# zx_tcp_serial.net
KiCad netlist of a schematic drawn in EasyEDA Pro
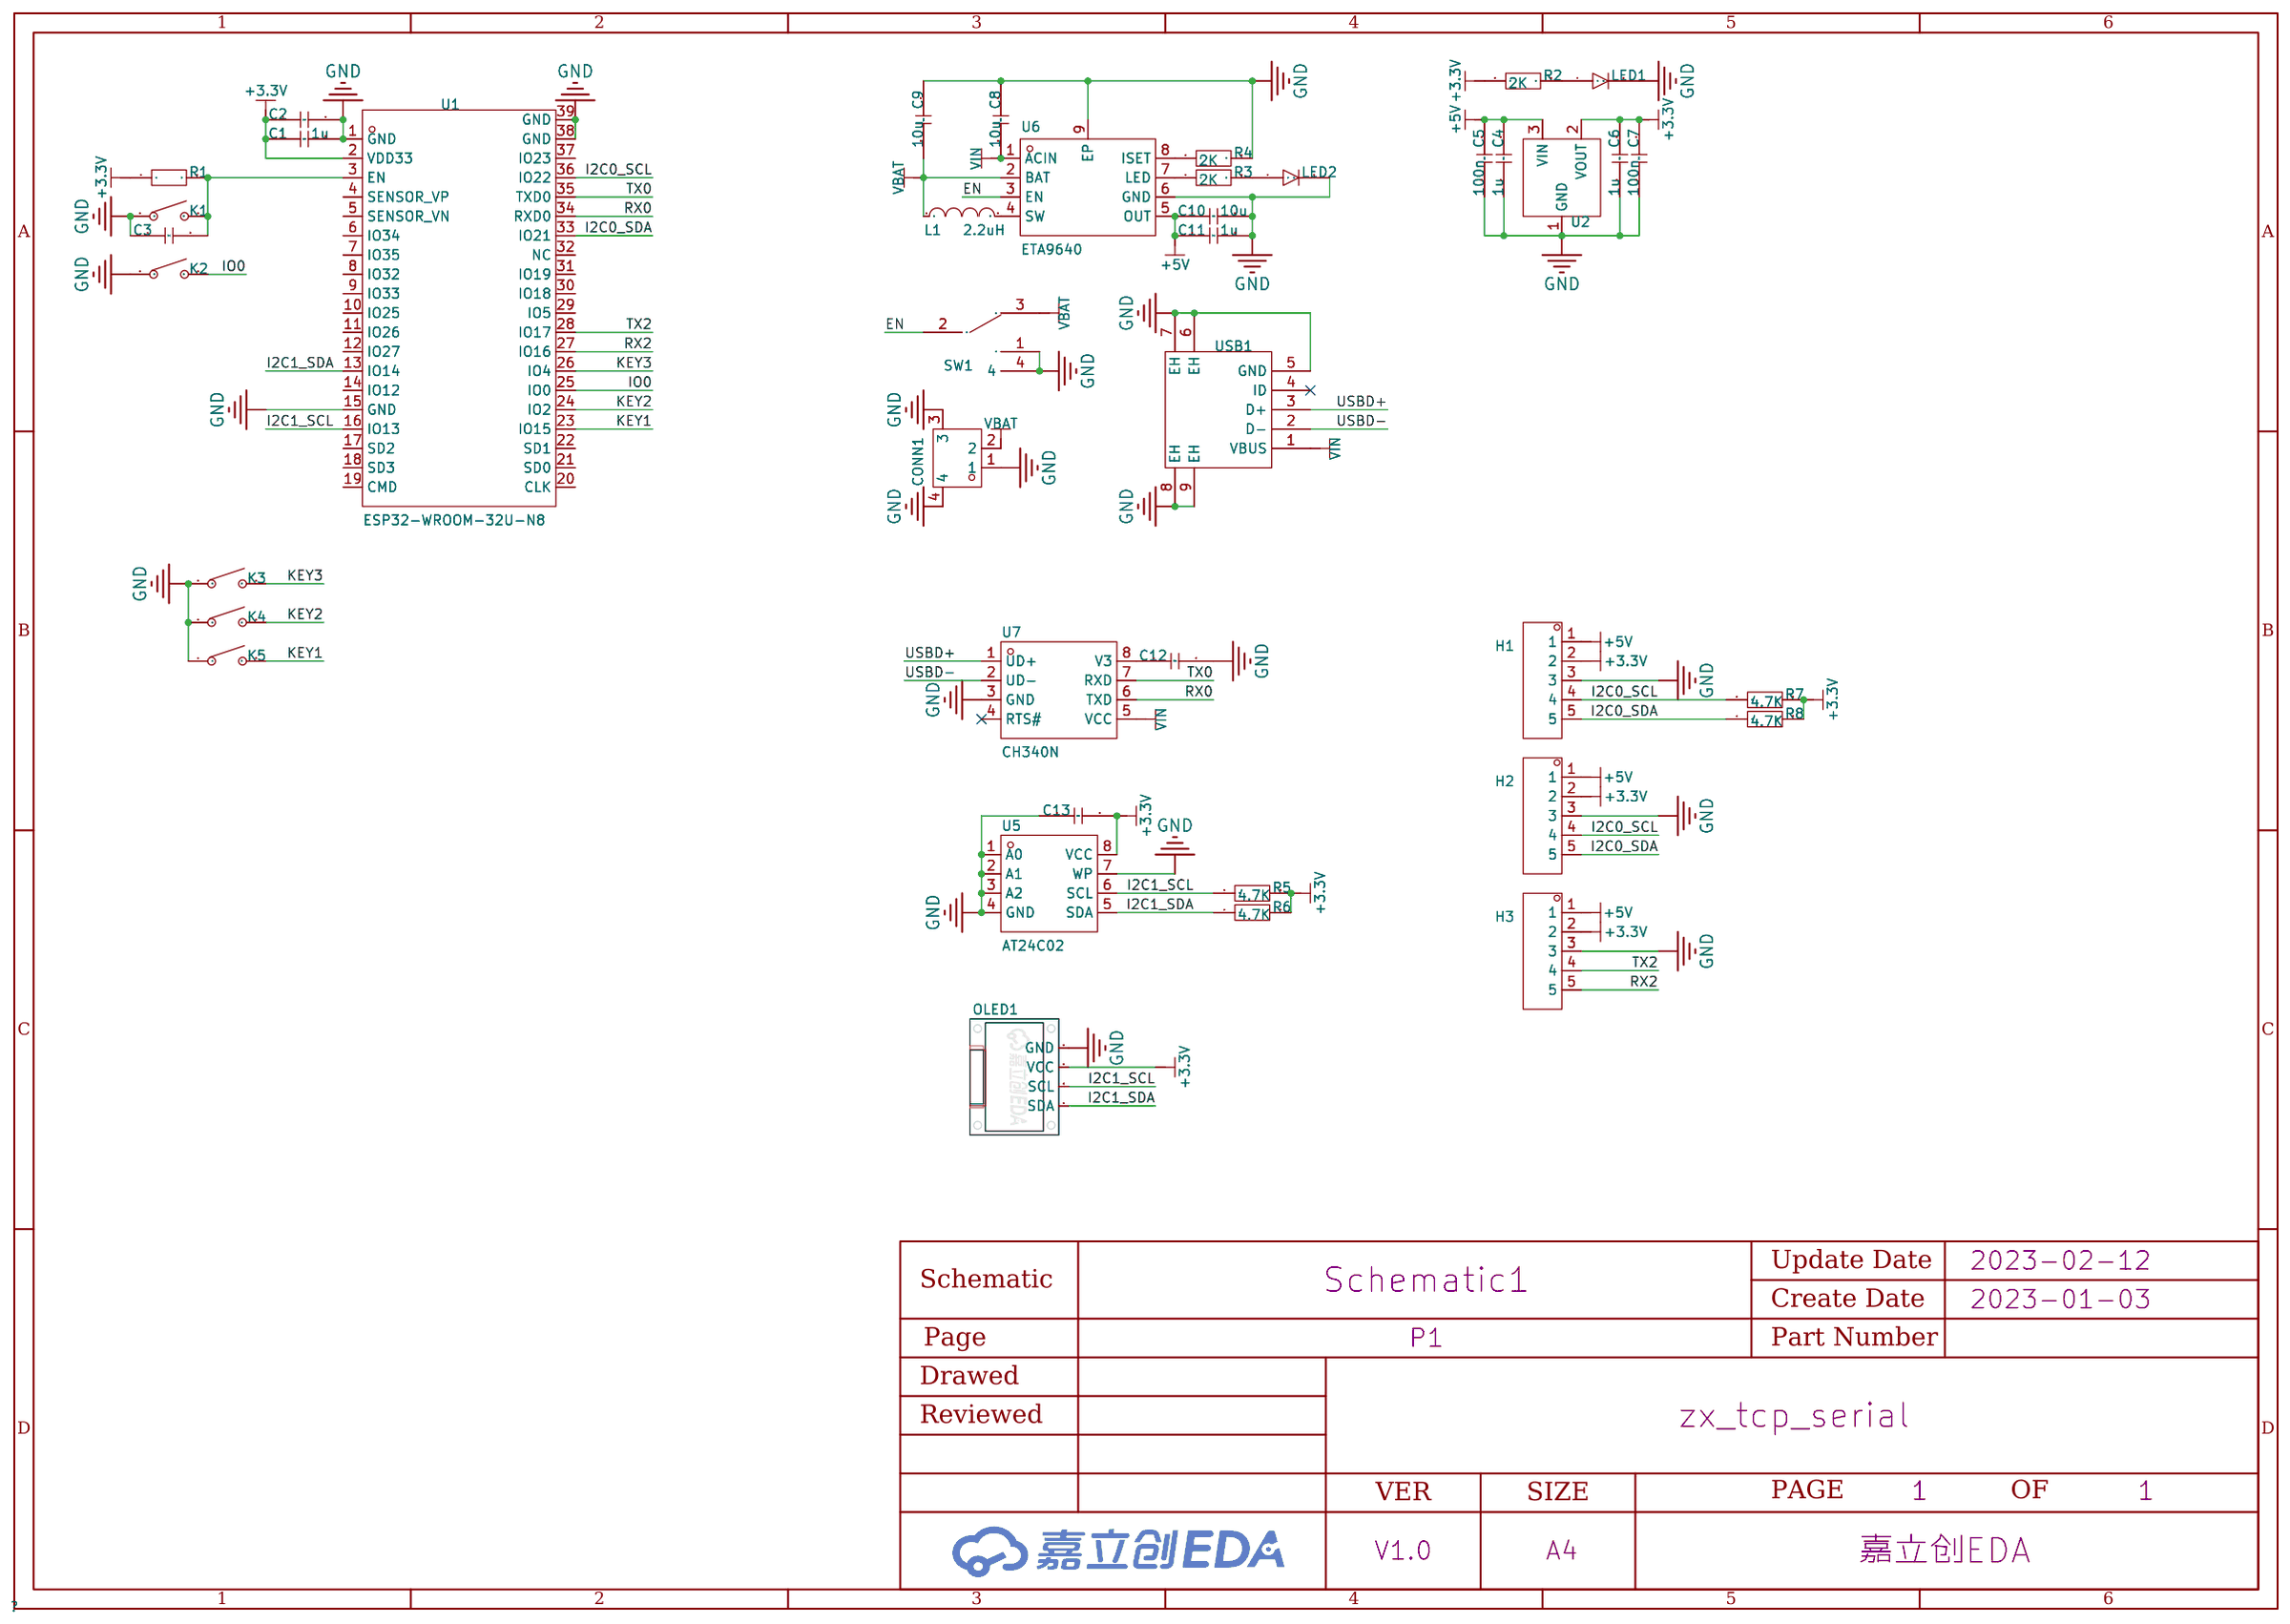
[diagram p0: schematic sheet]

(export (version "E")
  (design (tool "Eeschema 10.0.6"))
  (components
    (comp (ref "C1")
      (value "1u")
      (footprint "easyedapro:C0603")
      (libsource (lib "easyedapro") (part "C0603"))
    )
    (comp (ref "C2")
      (value "100n")
      (footprint "easyedapro:C0603")
      (libsource (lib "easyedapro") (part "C0603"))
    )
    (comp (ref "C3")
      (value "100n")
      (footprint "easyedapro:C0603")
      (libsource (lib "easyedapro") (part "C0603"))
    )
    (comp (ref "C4")
      (value "1u")
      (footprint "easyedapro:C0603")
      (libsource (lib "easyedapro") (part "C0603"))
    )
    (comp (ref "C5")
      (value "100n")
      (footprint "easyedapro:C0603")
      (libsource (lib "easyedapro") (part "C0603"))
    )
    (comp (ref "C6")
      (value "1u")
      (footprint "easyedapro:C0603")
      (libsource (lib "easyedapro") (part "C0603"))
    )
    (comp (ref "C7")
      (value "100n")
      (footprint "easyedapro:C0603")
      (libsource (lib "easyedapro") (part "C0603"))
    )
    (comp (ref "C8")
      (value "10u")
      (footprint "easyedapro:C0603")
      (libsource (lib "easyedapro") (part "C0603"))
    )
    (comp (ref "C9")
      (value "10u")
      (footprint "easyedapro:C0603")
      (libsource (lib "easyedapro") (part "C0603"))
    )
    (comp (ref "C10")
      (value "10u")
      (footprint "easyedapro:C0603")
      (libsource (lib "easyedapro") (part "C0603"))
    )
    (comp (ref "C11")
      (value "1u")
      (footprint "easyedapro:C0603")
      (libsource (lib "easyedapro") (part "C0603"))
    )
    (comp (ref "C12")
      (value "100n")
      (footprint "easyedapro:C0603")
      (libsource (lib "easyedapro") (part "C0603"))
    )
    (comp (ref "C13")
      (value "100n")
      (footprint "easyedapro:C0603")
      (libsource (lib "easyedapro") (part "C0603"))
    )
    (comp (ref "CONN1")
      (value "WAFER-SH1.0-2PWB")
      (footprint "easyedapro:CONN-SMD_2P-P1.00_XUNPU_WAFER-SH1.0-2PWB")
      (description "间距:1mm;插针结构:1x2P;排数:1;每排PIN数:2;公母:公型插针;安装方式:卧贴;额定电流:1A;工作温度范围:-25℃~+85℃;")
      (fields (field (name "Manufacturer") "XUNPU(讯普)"))
      (libsource (lib "easyedapro") (part "WAFER-SH1.0-2PWB"))
    )
    (comp (ref "H1")
      (value "~")
      (footprint "easyedapro:HDR-TH_5P-P2.54-V-M")
      (libsource (lib "easyedapro") (part "MTP125-1105S1"))
    )
    (comp (ref "H2")
      (value "~")
      (footprint "easyedapro:HDR-TH_5P-P2.54-V-M")
      (libsource (lib "easyedapro") (part "MTP125-1105S1"))
    )
    (comp (ref "H3")
      (value "~")
      (footprint "easyedapro:HDR-TH_5P-P2.54-V-M")
      (libsource (lib "easyedapro") (part "MTP125-1105S1"))
    )
    (comp (ref "K1")
      (value "~")
      (footprint "easyedapro:SW-SMD_L6.0-W3.6-LS8.0")
      (libsource (lib "easyedapro") (part "TOUCH_SWITCH"))
    )
    (comp (ref "K2")
      (value "~")
      (footprint "easyedapro:SW-SMD_L6.0-W3.6-LS8.0")
      (libsource (lib "easyedapro") (part "TOUCH_SWITCH"))
    )
    (comp (ref "K3")
      (value "~")
      (footprint "easyedapro:SW-SMD_L6.0-W3.6-LS8.0")
      (libsource (lib "easyedapro") (part "TOUCH_SWITCH"))
    )
    (comp (ref "K4")
      (value "~")
      (footprint "easyedapro:SW-SMD_L6.0-W3.6-LS8.0")
      (libsource (lib "easyedapro") (part "TOUCH_SWITCH"))
    )
    (comp (ref "K5")
      (value "~")
      (footprint "easyedapro:SW-SMD_L6.0-W3.6-LS8.0")
      (libsource (lib "easyedapro") (part "TOUCH_SWITCH"))
    )
    (comp (ref "L1")
      (value "2.2uH")
      (footprint "easyedapro:IND-SMD_L4.4-W4.2")
      (libsource (lib "easyedapro") (part "4.7UH/2.5A"))
    )
    (comp (ref "LED1")
      (value "green")
      (footprint "easyedapro:LED0603")
      (libsource (lib "easyedapro") (part "LED-G"))
    )
    (comp (ref "LED2")
      (value "red")
      (footprint "easyedapro:LED0603")
      (libsource (lib "easyedapro") (part "LED-R"))
    )
    (comp (ref "OLED1")
      (value "~")
      (footprint "easyedapro:OLED_0.96_4P")
      (libsource (lib "easyedapro") (part "OLED_0.96_4P"))
    )
    (comp (ref "R1")
      (value "10K")
      (footprint "easyedapro:R0603")
      (libsource (lib "easyedapro") (part "R0603"))
    )
    (comp (ref "R2")
      (value "2K")
      (footprint "easyedapro:R0603")
      (libsource (lib "easyedapro") (part "R0603"))
    )
    (comp (ref "R3")
      (value "2K")
      (footprint "easyedapro:R0603")
      (libsource (lib "easyedapro") (part "R0603"))
    )
    (comp (ref "R4")
      (value "2K")
      (footprint "easyedapro:R0603")
      (libsource (lib "easyedapro") (part "R0603"))
    )
    (comp (ref "R5")
      (value "4.7K")
      (footprint "easyedapro:R0603")
      (libsource (lib "easyedapro") (part "R0603"))
    )
    (comp (ref "R6")
      (value "4.7K")
      (footprint "easyedapro:R0603")
      (libsource (lib "easyedapro") (part "R0603"))
    )
    (comp (ref "R7")
      (value "4.7K")
      (footprint "easyedapro:R0603")
      (libsource (lib "easyedapro") (part "R0603"))
    )
    (comp (ref "R8")
      (value "4.7K")
      (footprint "easyedapro:R0603")
      (libsource (lib "easyedapro") (part "R0603"))
    )
    (comp (ref "SW1")
      (value "拨动开关/MSK01-AG1.5/7.8*1.5*4.2mm")
      (footprint "easyedapro:SW-TH_MSK01-AG1.5")
      (libsource (lib "easyedapro") (part "拨动开关/MSK01-AG1.5/7.8*1.5*4.2MM"))
    )
    (comp (ref "U1")
      (value "ESP32-WROOM-32U-N8")
      (footprint "easyedapro:WIFIM-SMD_39P-L19.2-W18.0-P1.27")
      (fields (field (name "Manufacturer") "ESPRESSIF(乐鑫)"))
      (libsource (lib "easyedapro") (part "ESP32-WROOM-32U(8MB)"))
    )
    (comp (ref "U2")
      (value "AMS1117-3.3")
      (footprint "easyedapro:SOT-89-3")
      (libsource (lib "easyedapro") (part "AMS1117"))
    )
    (comp (ref "U5")
      (value "AT24C02")
      (footprint "easyedapro:SOIC-8_L4.9-W3.9-P1.27-LS6.0-BL")
      (libsource (lib "easyedapro") (part "AT24C02"))
    )
    (comp (ref "U6")
      (value "ETA9640")
      (footprint "easyedapro:ESOP-8_L4.9-W3.9-P1.27-LS6.0-BL-EP")
      (libsource (lib "easyedapro") (part "ETA9640"))
    )
    (comp (ref "U7")
      (value "CH340N")
      (footprint "easyedapro:SOP-8_L5.0-W4.0-P1.27-LS6.0-BL")
      (fields (field (name "Manufacturer") "WCH(南京沁恒)"))
      (libsource (lib "easyedapro") (part "CH340N"))
    )
    (comp (ref "USB1")
      (value "KH-MICRO-SMT.J7.2-5P")
      (footprint "easyedapro:MICRO-USB-SMD_KH-MICRO-SMT.J7.2-5P")
      (description "连接器类型:Micro-B;标准:USB 2.0;公母:母座;触点数量:5;端口数量:1;安装方式:卧贴;额定电流 - 电源:1A;工作温度范围:-30℃~+80℃;")
      (fields (field (name "Manufacturer") "kinghelm(金航标)"))
      (libsource (lib "easyedapro") (part "KH-MICRO-SMT.J7.2-5P"))
    )
  )
  (nets
    (net (code "1") (name "+3.3V") (class "Default")
      (node (ref "C1") (pin "1") (pinfunction "1_1") (pintype "input"))
      (node (ref "C13") (pin "2") (pinfunction "2_2") (pintype "input"))
      (node (ref "C2") (pin "1") (pinfunction "1_1") (pintype "input"))
      (node (ref "C6") (pin "2") (pinfunction "2_2") (pintype "input"))
      (node (ref "C7") (pin "2") (pinfunction "2_2") (pintype "input"))
      (node (ref "H1") (pin "2") (pinfunction "2_2") (pintype "input"))
      (node (ref "H2") (pin "2") (pinfunction "2_2") (pintype "input"))
      (node (ref "H3") (pin "2") (pinfunction "2_2") (pintype "input"))
      (node (ref "OLED1") (pin "2") (pinfunction "VCC_2") (pintype "input"))
      (node (ref "R1") (pin "1") (pinfunction "1_1") (pintype "input"))
      (node (ref "R2") (pin "1") (pinfunction "1_1") (pintype "input"))
      (node (ref "R5") (pin "2") (pinfunction "2_2") (pintype "input"))
      (node (ref "R6") (pin "2") (pinfunction "2_2") (pintype "input"))
      (node (ref "R7") (pin "2") (pinfunction "2_2") (pintype "input"))
      (node (ref "R8") (pin "2") (pinfunction "2_2") (pintype "input"))
      (node (ref "U1") (pin "2") (pinfunction "VDD33_2") (pintype "input"))
      (node (ref "U2") (pin "2") (pinfunction "VOUT_2") (pintype "input"))
      (node (ref "U5") (pin "8") (pinfunction "VCC_8") (pintype "input"))
    )
    (net (code "2") (name "+5V") (class "Default")
      (node (ref "C10") (pin "1") (pinfunction "1_1") (pintype "input"))
      (node (ref "C11") (pin "1") (pinfunction "1_1") (pintype "input"))
      (node (ref "C4") (pin "2") (pinfunction "2_2") (pintype "input"))
      (node (ref "C5") (pin "2") (pinfunction "2_2") (pintype "input"))
      (node (ref "H1") (pin "1") (pinfunction "1_1") (pintype "input"))
      (node (ref "H2") (pin "1") (pinfunction "1_1") (pintype "input"))
      (node (ref "H3") (pin "1") (pinfunction "1_1") (pintype "input"))
      (node (ref "U2") (pin "3") (pinfunction "VIN_3") (pintype "input"))
      (node (ref "U6") (pin "5") (pinfunction "OUT_5") (pintype "input"))
    )
    (net (code "3") (name "/EN") (class "Default")
      (node (ref "SW1") (pin "2") (pinfunction "2_2") (pintype "input"))
      (node (ref "U6") (pin "3") (pinfunction "EN_3") (pintype "input"))
    )
    (net (code "4") (name "/I2C0_SCL") (class "Default")
      (node (ref "H1") (pin "4") (pinfunction "4_4") (pintype "input"))
      (node (ref "H2") (pin "4") (pinfunction "4_4") (pintype "input"))
      (node (ref "R7") (pin "1") (pinfunction "1_1") (pintype "input"))
      (node (ref "U1") (pin "36") (pinfunction "IO22_36") (pintype "input"))
    )
    (net (code "5") (name "/I2C0_SDA") (class "Default")
      (node (ref "H1") (pin "5") (pinfunction "5_5") (pintype "input"))
      (node (ref "H2") (pin "5") (pinfunction "5_5") (pintype "input"))
      (node (ref "R8") (pin "1") (pinfunction "1_1") (pintype "input"))
      (node (ref "U1") (pin "33") (pinfunction "IO21_33") (pintype "input"))
    )
    (net (code "6") (name "/I2C1_SCL") (class "Default")
      (node (ref "OLED1") (pin "3") (pinfunction "SCL_3") (pintype "input"))
      (node (ref "R5") (pin "1") (pinfunction "1_1") (pintype "input"))
      (node (ref "U1") (pin "16") (pinfunction "IO13_16") (pintype "input"))
      (node (ref "U5") (pin "6") (pinfunction "SCL_6") (pintype "input"))
    )
    (net (code "7") (name "/I2C1_SDA") (class "Default")
      (node (ref "OLED1") (pin "4") (pinfunction "SDA_4") (pintype "input"))
      (node (ref "R6") (pin "1") (pinfunction "1_1") (pintype "input"))
      (node (ref "U1") (pin "13") (pinfunction "IO14_13") (pintype "input"))
      (node (ref "U5") (pin "5") (pinfunction "SDA_5") (pintype "input"))
    )
    (net (code "8") (name "/IO0") (class "Default")
      (node (ref "K2") (pin "2") (pinfunction "2_2") (pintype "input"))
      (node (ref "U1") (pin "25") (pinfunction "IO0_25") (pintype "input"))
    )
    (net (code "9") (name "/KEY1") (class "Default")
      (node (ref "K5") (pin "2") (pinfunction "2_2") (pintype "input"))
      (node (ref "U1") (pin "23") (pinfunction "IO15_23") (pintype "input"))
    )
    (net (code "10") (name "/KEY2") (class "Default")
      (node (ref "K4") (pin "2") (pinfunction "2_2") (pintype "input"))
      (node (ref "U1") (pin "24") (pinfunction "IO2_24") (pintype "input"))
    )
    (net (code "11") (name "/KEY3") (class "Default")
      (node (ref "K3") (pin "2") (pinfunction "2_2") (pintype "input"))
      (node (ref "U1") (pin "26") (pinfunction "IO4_26") (pintype "input"))
    )
    (net (code "12") (name "/RX0") (class "Default")
      (node (ref "U1") (pin "34") (pinfunction "RXD0_34") (pintype "input"))
      (node (ref "U7") (pin "6") (pinfunction "TXD_6") (pintype "input"))
    )
    (net (code "13") (name "/RX2") (class "Default")
      (node (ref "H3") (pin "5") (pinfunction "5_5") (pintype "input"))
      (node (ref "U1") (pin "27") (pinfunction "IO16_27") (pintype "input"))
    )
    (net (code "14") (name "/TX0") (class "Default")
      (node (ref "U1") (pin "35") (pinfunction "TXD0_35") (pintype "input"))
      (node (ref "U7") (pin "7") (pinfunction "RXD_7") (pintype "input"))
    )
    (net (code "15") (name "/TX2") (class "Default")
      (node (ref "H3") (pin "4") (pinfunction "4_4") (pintype "input"))
      (node (ref "U1") (pin "28") (pinfunction "IO17_28") (pintype "input"))
    )
    (net (code "16") (name "/USBD+") (class "Default")
      (node (ref "U7") (pin "1") (pinfunction "UD+_1") (pintype "input"))
      (node (ref "USB1") (pin "3") (pinfunction "D+_3") (pintype "input"))
    )
    (net (code "17") (name "/USBD-") (class "Default")
      (node (ref "U7") (pin "2") (pinfunction "UD-_2") (pintype "input"))
      (node (ref "USB1") (pin "2") (pinfunction "D-_2") (pintype "input"))
    )
    (net (code "18") (name "GND") (class "Default")
      (node (ref "C1") (pin "2") (pinfunction "2_2") (pintype "input"))
      (node (ref "C10") (pin "2") (pinfunction "2_2") (pintype "input"))
      (node (ref "C11") (pin "2") (pinfunction "2_2") (pintype "input"))
      (node (ref "C12") (pin "2") (pinfunction "2_2") (pintype "input"))
      (node (ref "C13") (pin "1") (pinfunction "1_1") (pintype "input"))
      (node (ref "C2") (pin "2") (pinfunction "2_2") (pintype "input"))
      (node (ref "C3") (pin "1") (pinfunction "1_1") (pintype "input"))
      (node (ref "C4") (pin "1") (pinfunction "1_1") (pintype "input"))
      (node (ref "C5") (pin "1") (pinfunction "1_1") (pintype "input"))
      (node (ref "C6") (pin "1") (pinfunction "1_1") (pintype "input"))
      (node (ref "C7") (pin "1") (pinfunction "1_1") (pintype "input"))
      (node (ref "C8") (pin "2") (pinfunction "2_2") (pintype "input"))
      (node (ref "C9") (pin "2") (pinfunction "2_2") (pintype "input"))
      (node (ref "CONN1") (pin "1") (pinfunction "1_1") (pintype "input"))
      (node (ref "CONN1") (pin "3") (pinfunction "3_3") (pintype "input"))
      (node (ref "CONN1") (pin "4") (pinfunction "4_4") (pintype "input"))
      (node (ref "H1") (pin "3") (pinfunction "3_3") (pintype "input"))
      (node (ref "H2") (pin "3") (pinfunction "3_3") (pintype "input"))
      (node (ref "H3") (pin "3") (pinfunction "3_3") (pintype "input"))
      (node (ref "K1") (pin "1") (pinfunction "1_1") (pintype "input"))
      (node (ref "K2") (pin "1") (pinfunction "1_1") (pintype "input"))
      (node (ref "K3") (pin "1") (pinfunction "1_1") (pintype "input"))
      (node (ref "K4") (pin "1") (pinfunction "1_1") (pintype "input"))
      (node (ref "K5") (pin "1") (pinfunction "1_1") (pintype "input"))
      (node (ref "LED1") (pin "2") (pinfunction "2_2") (pintype "input"))
      (node (ref "LED2") (pin "2") (pinfunction "2_2") (pintype "input"))
      (node (ref "OLED1") (pin "1") (pinfunction "GND_1") (pintype "input"))
      (node (ref "R4") (pin "2") (pinfunction "2_2") (pintype "input"))
      (node (ref "SW1") (pin "1") (pinfunction "1_1") (pintype "input"))
      (node (ref "SW1") (pin "4") (pinfunction "4_4") (pintype "input"))
      (node (ref "U1") (pin "1") (pinfunction "GND_1") (pintype "input"))
      (node (ref "U1") (pin "15") (pinfunction "GND_15") (pintype "input"))
      (node (ref "U1") (pin "38") (pinfunction "GND_38") (pintype "input"))
      (node (ref "U1") (pin "39") (pinfunction "GND_39") (pintype "input"))
      (node (ref "U2") (pin "1") (pinfunction "GND_1") (pintype "input"))
      (node (ref "U5") (pin "1") (pinfunction "A0_1") (pintype "input"))
      (node (ref "U5") (pin "2") (pinfunction "A1_2") (pintype "input"))
      (node (ref "U5") (pin "3") (pinfunction "A2_3") (pintype "input"))
      (node (ref "U5") (pin "4") (pinfunction "GND_4") (pintype "input"))
      (node (ref "U5") (pin "7") (pinfunction "WP_7") (pintype "input"))
      (node (ref "U6") (pin "6") (pinfunction "GND_6") (pintype "input"))
      (node (ref "U6") (pin "9") (pinfunction "EP_9") (pintype "input"))
      (node (ref "U7") (pin "3") (pinfunction "GND_3") (pintype "input"))
      (node (ref "USB1") (pin "5") (pinfunction "GND_5") (pintype "input"))
      (node (ref "USB1") (pin "6") (pinfunction "EH_6") (pintype "input"))
      (node (ref "USB1") (pin "7") (pinfunction "EH_7") (pintype "input"))
      (node (ref "USB1") (pin "8") (pinfunction "EH_8") (pintype "input"))
      (node (ref "USB1") (pin "9") (pinfunction "EH_9") (pintype "input"))
    )
    (net (code "19") (name "Net-(LED1-Pad1)") (class "Default")
      (node (ref "LED1") (pin "1") (pinfunction "1_1") (pintype "input"))
      (node (ref "R2") (pin "2") (pinfunction "2_2") (pintype "input"))
    )
    (net (code "20") (name "Net-(LED2-Pad1)") (class "Default")
      (node (ref "LED2") (pin "1") (pinfunction "1_1") (pintype "input"))
      (node (ref "R3") (pin "2") (pinfunction "2_2") (pintype "input"))
    )
    (net (code "21") (name "Net-(U1-EN)") (class "Default")
      (node (ref "C3") (pin "2") (pinfunction "2_2") (pintype "input"))
      (node (ref "K1") (pin "2") (pinfunction "2_2") (pintype "input"))
      (node (ref "R1") (pin "2") (pinfunction "2_2") (pintype "input"))
      (node (ref "U1") (pin "3") (pinfunction "EN_3") (pintype "input"))
    )
    (net (code "22") (name "Net-(U6-ISET)") (class "Default")
      (node (ref "R4") (pin "1") (pinfunction "1_1") (pintype "input"))
      (node (ref "U6") (pin "8") (pinfunction "ISET_8") (pintype "input"))
    )
    (net (code "23") (name "Net-(U6-LED)") (class "Default")
      (node (ref "R3") (pin "1") (pinfunction "1_1") (pintype "input"))
      (node (ref "U6") (pin "7") (pinfunction "LED_7") (pintype "input"))
    )
    (net (code "24") (name "Net-(U6-SW)") (class "Default")
      (node (ref "L1") (pin "2") (pinfunction "2_2") (pintype "input"))
      (node (ref "U6") (pin "4") (pinfunction "SW_4") (pintype "input"))
    )
    (net (code "25") (name "Net-(U7-V3)") (class "Default")
      (node (ref "C12") (pin "1") (pinfunction "1_1") (pintype "input"))
      (node (ref "U7") (pin "8") (pinfunction "V3_8") (pintype "input"))
    )
    (net (code "26") (name "VBAT") (class "Default")
      (node (ref "C9") (pin "1") (pinfunction "1_1") (pintype "input"))
      (node (ref "CONN1") (pin "2") (pinfunction "2_2") (pintype "input"))
      (node (ref "L1") (pin "1") (pinfunction "1_1") (pintype "input"))
      (node (ref "SW1") (pin "3") (pinfunction "3_3") (pintype "input"))
      (node (ref "U6") (pin "2") (pinfunction "BAT_2") (pintype "input"))
    )
    (net (code "27") (name "VIN") (class "Default")
      (node (ref "C8") (pin "1") (pinfunction "1_1") (pintype "input"))
      (node (ref "U6") (pin "1") (pinfunction "ACIN_1") (pintype "input"))
      (node (ref "U7") (pin "5") (pinfunction "VCC_5") (pintype "input"))
      (node (ref "USB1") (pin "1") (pinfunction "VBUS_1") (pintype "input"))
    )
    (net (code "28") (name "unconnected-(U1-CLK-Pad20)") (class "Default")
      (node (ref "U1") (pin "20") (pinfunction "CLK_20") (pintype "input"))
    )
    (net (code "29") (name "unconnected-(U1-CMD-Pad19)") (class "Default")
      (node (ref "U1") (pin "19") (pinfunction "CMD_19") (pintype "input"))
    )
    (net (code "30") (name "unconnected-(U1-IO5-Pad29)") (class "Default")
      (node (ref "U1") (pin "29") (pinfunction "IO5_29") (pintype "input"))
    )
    (net (code "31") (name "unconnected-(U1-IO12-Pad14)") (class "Default")
      (node (ref "U1") (pin "14") (pinfunction "IO12_14") (pintype "input"))
    )
    (net (code "32") (name "unconnected-(U1-IO18-Pad30)") (class "Default")
      (node (ref "U1") (pin "30") (pinfunction "IO18_30") (pintype "input"))
    )
    (net (code "33") (name "unconnected-(U1-IO19-Pad31)") (class "Default")
      (node (ref "U1") (pin "31") (pinfunction "IO19_31") (pintype "input"))
    )
    (net (code "34") (name "unconnected-(U1-IO23-Pad37)") (class "Default")
      (node (ref "U1") (pin "37") (pinfunction "IO23_37") (pintype "input"))
    )
    (net (code "35") (name "unconnected-(U1-IO25-Pad10)") (class "Default")
      (node (ref "U1") (pin "10") (pinfunction "IO25_10") (pintype "input"))
    )
    (net (code "36") (name "unconnected-(U1-IO26-Pad11)") (class "Default")
      (node (ref "U1") (pin "11") (pinfunction "IO26_11") (pintype "input"))
    )
    (net (code "37") (name "unconnected-(U1-IO27-Pad12)") (class "Default")
      (node (ref "U1") (pin "12") (pinfunction "IO27_12") (pintype "input"))
    )
    (net (code "38") (name "unconnected-(U1-IO32-Pad8)") (class "Default")
      (node (ref "U1") (pin "8") (pinfunction "IO32_8") (pintype "input"))
    )
    (net (code "39") (name "unconnected-(U1-IO33-Pad9)") (class "Default")
      (node (ref "U1") (pin "9") (pinfunction "IO33_9") (pintype "input"))
    )
    (net (code "40") (name "unconnected-(U1-IO34-Pad6)") (class "Default")
      (node (ref "U1") (pin "6") (pinfunction "IO34_6") (pintype "input"))
    )
    (net (code "41") (name "unconnected-(U1-IO35-Pad7)") (class "Default")
      (node (ref "U1") (pin "7") (pinfunction "IO35_7") (pintype "input"))
    )
    (net (code "42") (name "unconnected-(U1-NC-Pad32)") (class "Default")
      (node (ref "U1") (pin "32") (pinfunction "NC_32") (pintype "input"))
    )
    (net (code "43") (name "unconnected-(U1-SD0-Pad21)") (class "Default")
      (node (ref "U1") (pin "21") (pinfunction "SD0_21") (pintype "input"))
    )
    (net (code "44") (name "unconnected-(U1-SD1-Pad22)") (class "Default")
      (node (ref "U1") (pin "22") (pinfunction "SD1_22") (pintype "input"))
    )
    (net (code "45") (name "unconnected-(U1-SD2-Pad17)") (class "Default")
      (node (ref "U1") (pin "17") (pinfunction "SD2_17") (pintype "input"))
    )
    (net (code "46") (name "unconnected-(U1-SD3-Pad18)") (class "Default")
      (node (ref "U1") (pin "18") (pinfunction "SD3_18") (pintype "input"))
    )
    (net (code "47") (name "unconnected-(U1-SENSOR_VN-Pad5)") (class "Default")
      (node (ref "U1") (pin "5") (pinfunction "SENSOR_VN_5") (pintype "input"))
    )
    (net (code "48") (name "unconnected-(U1-SENSOR_VP-Pad4)") (class "Default")
      (node (ref "U1") (pin "4") (pinfunction "SENSOR_VP_4") (pintype "input"))
    )
    (net (code "49") (name "unconnected-(U7-RTS#-Pad4)") (class "Default")
      (node (ref "U7") (pin "4") (pinfunction "RTS#_4") (pintype "input+no_connect"))
    )
    (net (code "50") (name "unconnected-(USB1-ID-Pad4)") (class "Default")
      (node (ref "USB1") (pin "4") (pinfunction "ID_4") (pintype "input+no_connect"))
    )
  )
)
